# Blaze.net
KiCad netlist of a schematic drawn in EAGLE
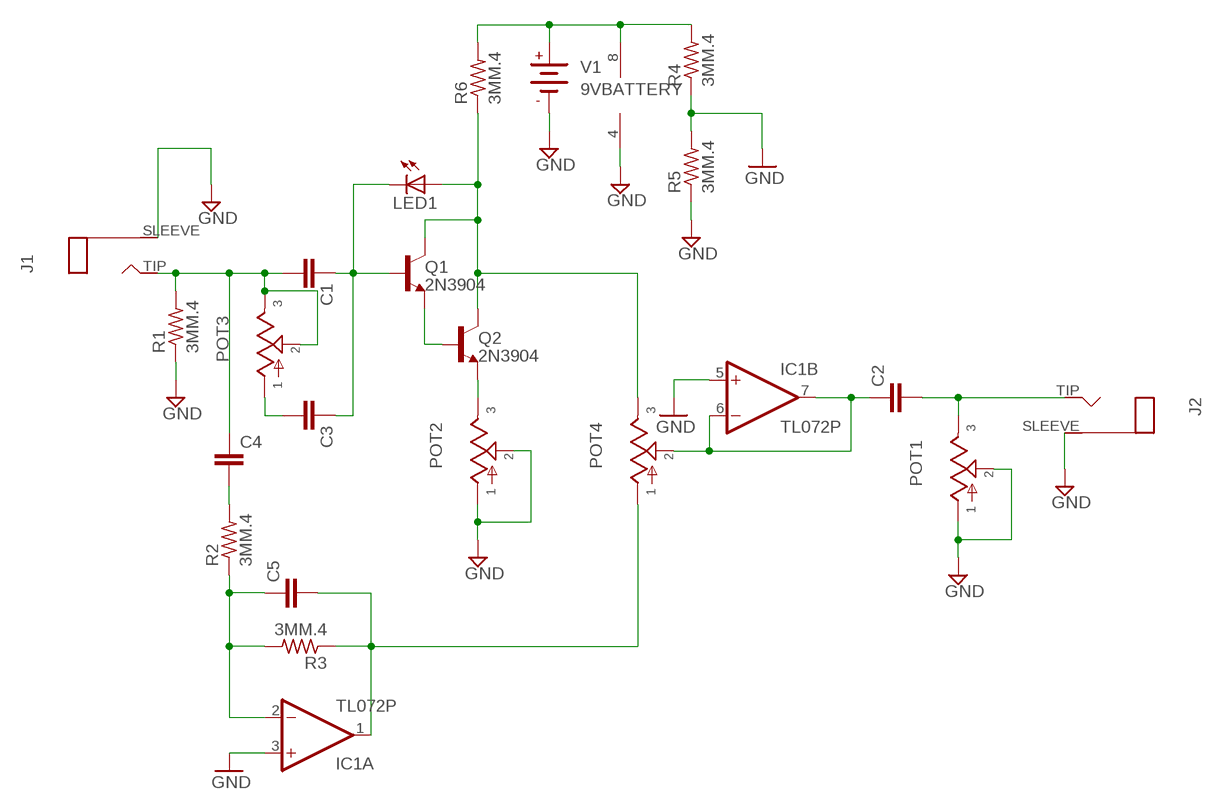
[diagram p0: schematic, sheet 1]

(export (version "E")
  (design (tool "Eeschema 10.0.6"))
  (components
    (comp (ref "C1")
      (value "050X030_0251")
      (footprint "eagle-import:050X030_025")
      (libsource (lib "eagle-import") (part "050X030_0251"))
    )
    (comp (ref "C2")
      (value "050X030_0251")
      (footprint "eagle-import:050X030_025")
      (libsource (lib "eagle-import") (part "050X030_0251"))
    )
    (comp (ref "C3")
      (value "050X030_0251")
      (footprint "eagle-import:050X030_025")
      (libsource (lib "eagle-import") (part "050X030_0251"))
    )
    (comp (ref "C4")
      (value "050X030_0251")
      (footprint "eagle-import:050X030_025")
      (libsource (lib "eagle-import") (part "050X030_0251"))
    )
    (comp (ref "C5")
      (value "050X030_0251")
      (footprint "eagle-import:050X030_025")
      (libsource (lib "eagle-import") (part "050X030_0251"))
    )
    (comp (ref "IC1")
      (value "TL072P")
      (footprint "eagle-import:DIL08")
      (libsource (lib "eagle-import") (part "TL072P"))
    )
    (comp (ref "J1")
      (value "MONOA")
      (footprint "eagle-import:MONO_JACK_A")
      (libsource (lib "eagle-import") (part "MONOA"))
    )
    (comp (ref "J2")
      (value "MONOA")
      (footprint "eagle-import:MONO_JACK_A")
      (libsource (lib "eagle-import") (part "MONOA"))
    )
    (comp (ref "LED1")
      (value "LED5MM")
      (footprint "eagle-import:LED5MM")
      (libsource (lib "eagle-import") (part "LED5MM"))
    )
    (comp (ref "POT1")
      (value "POT")
      (footprint "eagle-import:POT")
      (libsource (lib "eagle-import") (part "POT"))
    )
    (comp (ref "POT2")
      (value "POT")
      (footprint "eagle-import:POT")
      (libsource (lib "eagle-import") (part "POT"))
    )
    (comp (ref "POT3")
      (value "POT")
      (footprint "eagle-import:POT")
      (libsource (lib "eagle-import") (part "POT"))
    )
    (comp (ref "POT4")
      (value "POT")
      (footprint "eagle-import:POT")
      (libsource (lib "eagle-import") (part "POT"))
    )
    (comp (ref "Q1")
      (value "2N3904")
      (footprint "eagle-import:TO92-")
      (libsource (lib "eagle-import") (part "2N3904"))
    )
    (comp (ref "Q2")
      (value "2N3904")
      (footprint "eagle-import:TO92-")
      (libsource (lib "eagle-import") (part "2N3904"))
    )
    (comp (ref "R1")
      (value "3MM.4")
      (footprint "eagle-import:R0204_4")
      (libsource (lib "eagle-import") (part "3MM.4"))
    )
    (comp (ref "R2")
      (value "3MM.4")
      (footprint "eagle-import:R0204_4")
      (libsource (lib "eagle-import") (part "3MM.4"))
    )
    (comp (ref "R3")
      (value "3MM.4")
      (footprint "eagle-import:R0204_4")
      (libsource (lib "eagle-import") (part "3MM.4"))
    )
    (comp (ref "R4")
      (value "3MM.4")
      (footprint "eagle-import:R0204_4")
      (libsource (lib "eagle-import") (part "3MM.4"))
    )
    (comp (ref "R5")
      (value "3MM.4")
      (footprint "eagle-import:R0204_4")
      (libsource (lib "eagle-import") (part "3MM.4"))
    )
    (comp (ref "R6")
      (value "3MM.4")
      (footprint "eagle-import:R0204_4")
      (libsource (lib "eagle-import") (part "3MM.4"))
    )
    (comp (ref "V1")
      (value "9VBATTERY")
      (footprint "eagle-import:AB9V")
      (libsource (lib "eagle-import") (part "9VBATTERY"))
    )
  )
  (nets
    (net (code "1") (name "GND") (class "Default")
      (node (ref "IC1") (pin "3") (pinfunction "+IN_3") (pintype "input"))
      (node (ref "IC1") (pin "4") (pinfunction "V-_4") (pintype "power_in"))
      (node (ref "IC1") (pin "5") (pinfunction "+IN_5") (pintype "input"))
      (node (ref "J1") (pin "SLEEVE") (pinfunction "SLEEVE_SLEEVE") (pintype "passive"))
      (node (ref "J2") (pin "SLEEVE") (pinfunction "SLEEVE_SLEEVE") (pintype "passive"))
      (node (ref "POT1") (pin "1") (pinfunction "1_1") (pintype "passive"))
      (node (ref "POT1") (pin "2") (pinfunction "2_2") (pintype "passive"))
      (node (ref "POT2") (pin "1") (pinfunction "1_1") (pintype "passive"))
      (node (ref "POT2") (pin "2") (pinfunction "2_2") (pintype "passive"))
      (node (ref "R1") (pin "1") (pinfunction "1_1") (pintype "passive"))
      (node (ref "R4") (pin "1") (pinfunction "1_1") (pintype "passive"))
      (node (ref "R5") (pin "1") (pinfunction "1_1") (pintype "passive"))
      (node (ref "R5") (pin "2") (pinfunction "2_2") (pintype "passive"))
      (node (ref "V1") (pin "-") (pinfunction "-_-") (pintype "passive"))
    )
    (net (code "2") (name "Net-(C1-Pad2)") (class "Default")
      (node (ref "C1") (pin "2") (pinfunction "2_2") (pintype "passive"))
      (node (ref "C4") (pin "1") (pinfunction "1_1") (pintype "passive"))
      (node (ref "J1") (pin "TIP") (pinfunction "TIP_TIP") (pintype "passive"))
      (node (ref "POT3") (pin "2") (pinfunction "2_2") (pintype "passive"))
      (node (ref "POT3") (pin "3") (pinfunction "3_3") (pintype "passive"))
      (node (ref "R1") (pin "2") (pinfunction "2_2") (pintype "passive"))
    )
    (net (code "3") (name "Net-(C2-Pad2)") (class "Default")
      (node (ref "C2") (pin "2") (pinfunction "2_2") (pintype "passive"))
      (node (ref "J2") (pin "TIP") (pinfunction "TIP_TIP") (pintype "passive"))
      (node (ref "POT1") (pin "3") (pinfunction "3_3") (pintype "passive"))
    )
    (net (code "4") (name "Net-(C3-Pad2)") (class "Default")
      (node (ref "C3") (pin "2") (pinfunction "2_2") (pintype "passive"))
      (node (ref "POT3") (pin "1") (pinfunction "1_1") (pintype "passive"))
    )
    (net (code "5") (name "Net-(C4-Pad2)") (class "Default")
      (node (ref "C4") (pin "2") (pinfunction "2_2") (pintype "passive"))
      (node (ref "R2") (pin "2") (pinfunction "2_2") (pintype "passive"))
    )
    (net (code "6") (name "Net-(IC1A--IN)") (class "Default")
      (node (ref "C5") (pin "1") (pinfunction "1_1") (pintype "passive"))
      (node (ref "IC1") (pin "2") (pinfunction "-IN_2") (pintype "input"))
      (node (ref "R2") (pin "1") (pinfunction "1_1") (pintype "passive"))
      (node (ref "R3") (pin "2") (pinfunction "2_2") (pintype "passive"))
    )
    (net (code "7") (name "Net-(IC1A-OUT)") (class "Default")
      (node (ref "C5") (pin "2") (pinfunction "2_2") (pintype "passive"))
      (node (ref "IC1") (pin "1") (pinfunction "OUT_1") (pintype "output"))
      (node (ref "POT4") (pin "1") (pinfunction "1_1") (pintype "passive"))
      (node (ref "R3") (pin "1") (pinfunction "1_1") (pintype "passive"))
    )
    (net (code "8") (name "Net-(IC1B--IN)") (class "Default")
      (node (ref "C2") (pin "1") (pinfunction "1_1") (pintype "passive"))
      (node (ref "IC1") (pin "6") (pinfunction "-IN_6") (pintype "input"))
      (node (ref "IC1") (pin "7") (pinfunction "OUT_7") (pintype "output"))
      (node (ref "POT4") (pin "2") (pinfunction "2_2") (pintype "passive"))
    )
    (net (code "9") (name "Net-(IC1C-V+)") (class "Default")
      (node (ref "IC1") (pin "8") (pinfunction "V+_8") (pintype "power_in"))
      (node (ref "R4") (pin "2") (pinfunction "2_2") (pintype "passive"))
      (node (ref "R6") (pin "2") (pinfunction "2_2") (pintype "passive"))
      (node (ref "V1") (pin "+") (pinfunction "+_+") (pintype "passive"))
    )
    (net (code "10") (name "Net-(LED1-C)") (class "Default")
      (node (ref "C1") (pin "1") (pinfunction "1_1") (pintype "passive"))
      (node (ref "C3") (pin "1") (pinfunction "1_1") (pintype "passive"))
      (node (ref "LED1") (pin "K") (pinfunction "C_K") (pintype "passive"))
      (node (ref "Q1") (pin "2") (pinfunction "B_2") (pintype "passive"))
    )
    (net (code "11") (name "Net-(Q1-C)") (class "Default")
      (node (ref "LED1") (pin "A") (pinfunction "A_A") (pintype "passive"))
      (node (ref "POT4") (pin "3") (pinfunction "3_3") (pintype "passive"))
      (node (ref "Q1") (pin "1") (pinfunction "C_1") (pintype "passive"))
      (node (ref "Q2") (pin "1") (pinfunction "C_1") (pintype "passive"))
      (node (ref "R6") (pin "1") (pinfunction "1_1") (pintype "passive"))
    )
    (net (code "12") (name "Net-(Q1-E)") (class "Default")
      (node (ref "Q1") (pin "3") (pinfunction "E_3") (pintype "passive"))
      (node (ref "Q2") (pin "2") (pinfunction "B_2") (pintype "passive"))
    )
    (net (code "13") (name "Net-(Q2-E)") (class "Default")
      (node (ref "POT2") (pin "3") (pinfunction "3_3") (pintype "passive"))
      (node (ref "Q2") (pin "3") (pinfunction "E_3") (pintype "passive"))
    )
  )
)
